# react4.net
KiCad netlist of a schematic drawn in Altium Designer
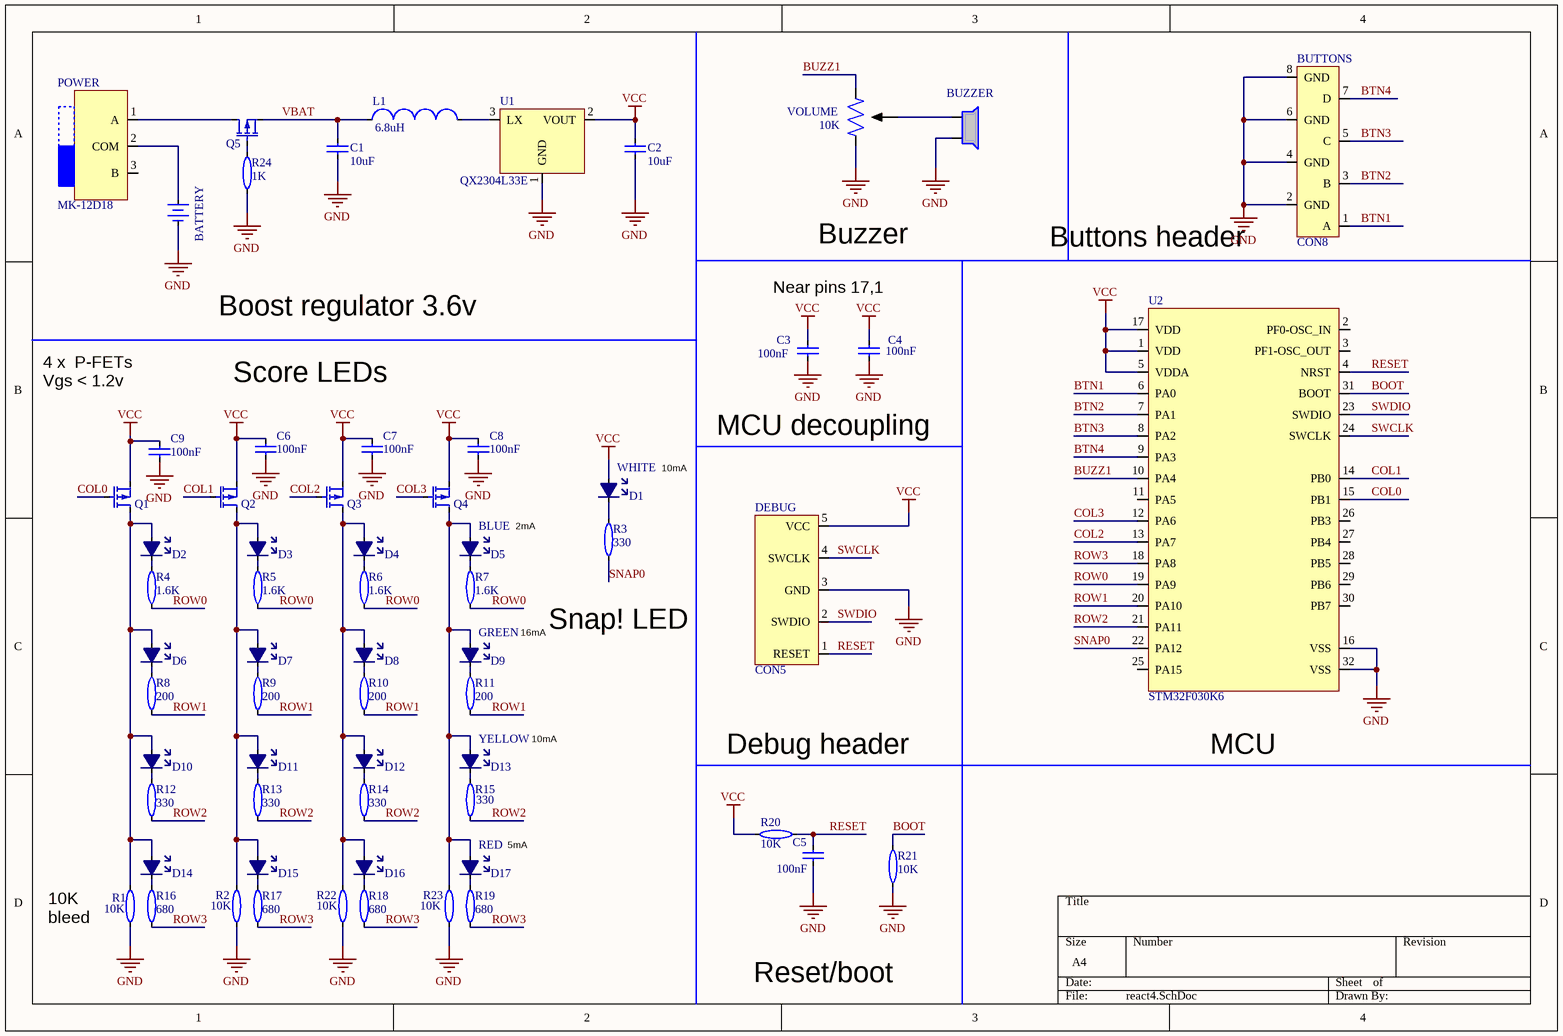
[diagram p0: react4.SchDoc]

(export (version "E")
  (design (tool "Eeschema 10.0.6"))
  (components
    (comp (ref "BATTERY")
      (value "BATTERY")
      (footprint "BATTERY_CONNECTOR")
      (libsource (lib "react4") (part "BATTERY"))
    )
    (comp (ref "BUTTONS")
      (value "CON8")
      (footprint "CON8")
      (description "2 x 4 2.54mm IDC board connector")
      (libsource (lib "react4") (part "CON8"))
    )
    (comp (ref "BUZZER")
      (value "BUZZER")
      (footprint "PIEZO_BUZZER")
      (description "3V 12mm piezo buzzer")
      (libsource (lib "react4") (part "BUZZER"))
    )
    (comp (ref "C1")
      (value "10uF")
      (footprint "CAPC_1206_3216X16L")
      (description "Capacitor")
      (fields (field (name "Comment") "CAPACITOR"))
      (libsource (lib "react4") (part "CAPACITOR"))
    )
    (comp (ref "C2")
      (value "10uF")
      (footprint "CAPC_1206_3216X16L")
      (description "Capacitor")
      (fields (field (name "Comment") "CAPACITOR"))
      (libsource (lib "react4") (part "CAPACITOR"))
    )
    (comp (ref "C3")
      (value "100nF")
      (footprint "CAPC_0603_1608X08L")
      (description "Capacitor")
      (fields (field (name "Comment") "CAPACITOR"))
      (libsource (lib "react4") (part "CAPACITOR"))
    )
    (comp (ref "C4")
      (value "100nF")
      (footprint "CAPC_0603_1608X08L")
      (description "Capacitor")
      (fields (field (name "Comment") "CAPACITOR"))
      (libsource (lib "react4") (part "CAPACITOR"))
    )
    (comp (ref "C5")
      (value "100nF")
      (footprint "CAPC_0603_1608X08L")
      (description "Capacitor")
      (fields (field (name "Comment") "CAPACITOR"))
      (libsource (lib "react4") (part "CAPACITOR"))
    )
    (comp (ref "C6")
      (value "100nF")
      (footprint "CAPC_0603_1608X08L")
      (description "Capacitor")
      (fields (field (name "Comment") "CAPACITOR"))
      (libsource (lib "react4") (part "CAPACITOR"))
    )
    (comp (ref "C7")
      (value "100nF")
      (footprint "CAPC_0603_1608X08L")
      (description "Capacitor")
      (fields (field (name "Comment") "CAPACITOR"))
      (libsource (lib "react4") (part "CAPACITOR"))
    )
    (comp (ref "C8")
      (value "100nF")
      (footprint "CAPC_0603_1608X08L")
      (description "Capacitor")
      (fields (field (name "Comment") "CAPACITOR"))
      (libsource (lib "react4") (part "CAPACITOR"))
    )
    (comp (ref "C9")
      (value "100nF")
      (footprint "CAPC_0603_1608X08L")
      (description "Capacitor")
      (fields (field (name "Comment") "CAPACITOR"))
      (libsource (lib "react4") (part "CAPACITOR"))
    )
    (comp (ref "D1")
      (value "WHITE")
      (footprint "LED WHITE")
      (description "5mm through hole LED")
      (libsource (lib "react4") (part "LED"))
    )
    (comp (ref "D2")
      (value "BLUE")
      (footprint "LED BLUE")
      (description "5mm through hole LED")
      (libsource (lib "react4") (part "LED"))
    )
    (comp (ref "D3")
      (value "BLUE")
      (footprint "LED BLUE")
      (description "5mm through hole LED")
      (libsource (lib "react4") (part "LED"))
    )
    (comp (ref "D4")
      (value "BLUE")
      (footprint "LED BLUE")
      (description "5mm through hole LED")
      (libsource (lib "react4") (part "LED"))
    )
    (comp (ref "D5")
      (value "BLUE")
      (footprint "LED BLUE")
      (description "5mm through hole LED")
      (libsource (lib "react4") (part "LED"))
    )
    (comp (ref "D6")
      (value "GREEN")
      (footprint "LED GREEN")
      (description "5mm through hole LED")
      (libsource (lib "react4") (part "LED"))
    )
    (comp (ref "D7")
      (value "GREEN")
      (footprint "LED GREEN")
      (description "5mm through hole LED")
      (libsource (lib "react4") (part "LED"))
    )
    (comp (ref "D8")
      (value "GREEN")
      (footprint "LED GREEN")
      (description "5mm through hole LED")
      (libsource (lib "react4") (part "LED"))
    )
    (comp (ref "D9")
      (value "GREEN")
      (footprint "LED GREEN")
      (description "5mm through hole LED")
      (libsource (lib "react4") (part "LED"))
    )
    (comp (ref "D10")
      (value "YELLOW")
      (footprint "LED YELLOW")
      (description "5mm through hole LED")
      (libsource (lib "react4") (part "LED"))
    )
    (comp (ref "D11")
      (value "YELLOW")
      (footprint "LED YELLOW")
      (description "5mm through hole LED")
      (libsource (lib "react4") (part "LED"))
    )
    (comp (ref "D12")
      (value "YELLOW")
      (footprint "LED YELLOW")
      (description "5mm through hole LED")
      (libsource (lib "react4") (part "LED"))
    )
    (comp (ref "D13")
      (value "YELLOW")
      (footprint "LED YELLOW")
      (description "5mm through hole LED")
      (libsource (lib "react4") (part "LED"))
    )
    (comp (ref "D14")
      (value "RED")
      (footprint "LED RED")
      (description "5mm through hole LED")
      (libsource (lib "react4") (part "LED"))
    )
    (comp (ref "D15")
      (value "RED")
      (footprint "LED RED")
      (description "5mm through hole LED")
      (libsource (lib "react4") (part "LED"))
    )
    (comp (ref "D16")
      (value "RED")
      (footprint "LED RED")
      (description "5mm through hole LED")
      (libsource (lib "react4") (part "LED"))
    )
    (comp (ref "D17")
      (value "RED")
      (footprint "LED RED")
      (description "5mm through hole LED")
      (libsource (lib "react4") (part "LED"))
    )
    (comp (ref "DEBUG") (value "CON5") (footprint "CON5") (libsource (lib "react4") (part "CON5")))
    (comp (ref "L1")
      (value "6.8uH")
      (footprint "Chip2PinSM127P600-8N")
      (description "200mA 1206 SMD Inductor")
      (fields (field (name "Comment") "INDUCTOR"))
      (libsource (lib "react4") (part "INDUCTOR"))
    )
    (comp (ref "POWER")
      (value "MK-12D18")
      (footprint "MK-12D18")
      (description "DIP,9.1x3.5x3.5mm Toggle Switch")
      (libsource (lib "react4") (part "SPDT SWITCH"))
    )
    (comp (ref "Q1")
      (value "NX2301P")
      (footprint "SOT95P237X110-3L")
      (description "P-MOSFET -20V -2A 400mW NX2301P or equivalent")
      (libsource (lib "react4") (part "MOSFET-P"))
    )
    (comp (ref "Q2")
      (value "NX2301P")
      (footprint "SOT95P237X110-3L")
      (description "P-MOSFET -20V -2A 400mW NX2301P or equivalent")
      (libsource (lib "react4") (part "MOSFET-P"))
    )
    (comp (ref "Q3")
      (value "NX2301P")
      (footprint "SOT95P237X110-3L")
      (description "P-MOSFET -20V -2A 400mW NX2301P or equivalent")
      (libsource (lib "react4") (part "MOSFET-P"))
    )
    (comp (ref "Q4")
      (value "NX2301P")
      (footprint "SOT95P237X110-3L")
      (description "P-MOSFET -20V -2A 400mW NX2301P or equivalent")
      (libsource (lib "react4") (part "MOSFET-P"))
    )
    (comp (ref "Q5")
      (value "NX2301P")
      (footprint "SOT95P237X110-3L")
      (description "P-MOSFET -20V -2A 400mW NX2301P or equivalent")
      (libsource (lib "react4") (part "MOSFET-P"))
    )
    (comp (ref "R1")
      (value "10K")
      (footprint "RESC_0603_1608X08L")
      (description "125mW 0603 SMD resistor")
      (fields (field (name "Comment") "RESISTOR"))
      (libsource (lib "react4") (part "RESISTOR"))
    )
    (comp (ref "R2")
      (value "10K")
      (footprint "RESC_0603_1608X08L")
      (description "125mW 0603 SMD resistor")
      (fields (field (name "Comment") "RESISTOR"))
      (libsource (lib "react4") (part "RESISTOR"))
    )
    (comp (ref "R3")
      (value "330")
      (footprint "RESC_0603_1608X08L")
      (description "125mW 0603 SMD resistor")
      (fields (field (name "Comment") "RESISTOR"))
      (libsource (lib "react4") (part "RESISTOR"))
    )
    (comp (ref "R4")
      (value "1.6K")
      (footprint "RESC_0603_1608X08L")
      (description "125mW 0603 SMD resistor")
      (fields (field (name "Comment") "RESISTOR"))
      (libsource (lib "react4") (part "RESISTOR"))
    )
    (comp (ref "R5")
      (value "1.6K")
      (footprint "RESC_0603_1608X08L")
      (description "125mW 0603 SMD resistor")
      (fields (field (name "Comment") "RESISTOR"))
      (libsource (lib "react4") (part "RESISTOR"))
    )
    (comp (ref "R6")
      (value "1.6K")
      (footprint "RESC_0603_1608X08L")
      (description "125mW 0603 SMD resistor")
      (fields (field (name "Comment") "RESISTOR"))
      (libsource (lib "react4") (part "RESISTOR"))
    )
    (comp (ref "R7")
      (value "1.6K")
      (footprint "RESC_0603_1608X08L")
      (description "125mW 0603 SMD resistor")
      (fields (field (name "Comment") "RESISTOR"))
      (libsource (lib "react4") (part "RESISTOR"))
    )
    (comp (ref "R8")
      (value "200")
      (footprint "RESC_0603_1608X08L")
      (description "125mW 0603 SMD resistor")
      (fields (field (name "Comment") "RESISTOR"))
      (libsource (lib "react4") (part "RESISTOR"))
    )
    (comp (ref "R9")
      (value "200")
      (footprint "RESC_0603_1608X08L")
      (description "125mW 0603 SMD resistor")
      (fields (field (name "Comment") "RESISTOR"))
      (libsource (lib "react4") (part "RESISTOR"))
    )
    (comp (ref "R10")
      (value "200")
      (footprint "RESC_0603_1608X08L")
      (description "125mW 0603 SMD resistor")
      (fields (field (name "Comment") "RESISTOR"))
      (libsource (lib "react4") (part "RESISTOR"))
    )
    (comp (ref "R11")
      (value "200")
      (footprint "RESC_0603_1608X08L")
      (description "125mW 0603 SMD resistor")
      (fields (field (name "Comment") "RESISTOR"))
      (libsource (lib "react4") (part "RESISTOR"))
    )
    (comp (ref "R12")
      (value "330")
      (footprint "RESC_0603_1608X08L")
      (description "125mW 0603 SMD resistor")
      (fields (field (name "Comment") "RESISTOR"))
      (libsource (lib "react4") (part "RESISTOR"))
    )
    (comp (ref "R13")
      (value "330")
      (footprint "RESC_0603_1608X08L")
      (description "125mW 0603 SMD resistor")
      (fields (field (name "Comment") "RESISTOR"))
      (libsource (lib "react4") (part "RESISTOR"))
    )
    (comp (ref "R14")
      (value "330")
      (footprint "RESC_0603_1608X08L")
      (description "125mW 0603 SMD resistor")
      (fields (field (name "Comment") "RESISTOR"))
      (libsource (lib "react4") (part "RESISTOR"))
    )
    (comp (ref "R15")
      (value "330")
      (footprint "RESC_0603_1608X08L")
      (description "125mW 0603 SMD resistor")
      (fields (field (name "Comment") "RESISTOR"))
      (libsource (lib "react4") (part "RESISTOR"))
    )
    (comp (ref "R16")
      (value "680")
      (footprint "RESC_0603_1608X08L")
      (description "125mW 0603 SMD resistor")
      (fields (field (name "Comment") "RESISTOR"))
      (libsource (lib "react4") (part "RESISTOR"))
    )
    (comp (ref "R17")
      (value "680")
      (footprint "RESC_0603_1608X08L")
      (description "125mW 0603 SMD resistor")
      (fields (field (name "Comment") "RESISTOR"))
      (libsource (lib "react4") (part "RESISTOR"))
    )
    (comp (ref "R18")
      (value "680")
      (footprint "RESC_0603_1608X08L")
      (description "125mW 0603 SMD resistor")
      (fields (field (name "Comment") "RESISTOR"))
      (libsource (lib "react4") (part "RESISTOR"))
    )
    (comp (ref "R19")
      (value "680")
      (footprint "RESC_0603_1608X08L")
      (description "125mW 0603 SMD resistor")
      (fields (field (name "Comment") "RESISTOR"))
      (libsource (lib "react4") (part "RESISTOR"))
    )
    (comp (ref "R20")
      (value "10K")
      (footprint "RESC_0603_1608X08L")
      (description "125mW 0603 SMD resistor")
      (fields (field (name "Comment") "RESISTOR"))
      (libsource (lib "react4") (part "RESISTOR"))
    )
    (comp (ref "R21")
      (value "10K")
      (footprint "RESC_0603_1608X08L")
      (description "125mW 0603 SMD resistor")
      (fields (field (name "Comment") "RESISTOR"))
      (libsource (lib "react4") (part "RESISTOR"))
    )
    (comp (ref "R22")
      (value "10K")
      (footprint "RESC_0603_1608X08L")
      (description "125mW 0603 SMD resistor")
      (fields (field (name "Comment") "RESISTOR"))
      (libsource (lib "react4") (part "RESISTOR"))
    )
    (comp (ref "R23")
      (value "10K")
      (footprint "RESC_0603_1608X08L")
      (description "125mW 0603 SMD resistor")
      (fields (field (name "Comment") "RESISTOR"))
      (libsource (lib "react4") (part "RESISTOR"))
    )
    (comp (ref "R24")
      (value "1K")
      (footprint "RESC_0603_1608X08L")
      (description "125mW 0603 SMD resistor")
      (fields (field (name "Comment") "RESISTOR"))
      (libsource (lib "react4") (part "RESISTOR"))
    )
    (comp (ref "U1")
      (value "QX2304L33E")
      (footprint "SOT89-150P350X160-3L")
      (description "3.3v boost regulator 1A 0.5W")
      (libsource (lib "react4") (part "QX2304L33E"))
    )
    (comp (ref "U2")
      (value "STM32F030K6")
      (footprint "TQFP80P900X900X160-32L")
      (description "STM32F030K6 QFP32 48MHz")
      (libsource (lib "react4") (part "STM32F030K6"))
    )
    (comp (ref "VOLUME")
      (value "10K")
      (footprint "POTENTIOMETER")
      (description "10K audio pot 16x2mm thumbwheel")
      (fields (field (name "Comment") "POTENTIOMETER"))
      (libsource (lib "react4") (part "POTENTIOMETER"))
    )
  )
  (nets
    (net (code "1") (name "/BOOT") (class "Default")
      (node (ref "R21") (pin "1") (pinfunction "1_1") (pintype "passive"))
      (node (ref "U2") (pin "31") (pinfunction "BOOT_31") (pintype "power_in"))
    )
    (net (code "2") (name "/BTN1") (class "Default")
      (node (ref "BUTTONS") (pin "1") (pinfunction "A_1") (pintype "power_in"))
      (node (ref "U2") (pin "6") (pinfunction "PA0_6") (pintype "power_in"))
    )
    (net (code "3") (name "/BTN2") (class "Default")
      (node (ref "BUTTONS") (pin "3") (pinfunction "B_3") (pintype "power_in"))
      (node (ref "U2") (pin "7") (pinfunction "PA1_7") (pintype "power_in"))
    )
    (net (code "4") (name "/BTN3") (class "Default")
      (node (ref "BUTTONS") (pin "5") (pinfunction "C_5") (pintype "power_in"))
      (node (ref "U2") (pin "8") (pinfunction "PA2_8") (pintype "power_in"))
    )
    (net (code "5") (name "/BTN4") (class "Default")
      (node (ref "BUTTONS") (pin "7") (pinfunction "D_7") (pintype "power_in"))
      (node (ref "U2") (pin "9") (pinfunction "PA3_9") (pintype "power_in"))
    )
    (net (code "6") (name "/BUZZ1") (class "Default")
      (node (ref "U2") (pin "10") (pinfunction "PA4_10") (pintype "power_in"))
      (node (ref "VOLUME") (pin "1") (pinfunction "1_1") (pintype "power_in"))
    )
    (net (code "7") (name "/COL0") (class "Default")
      (node (ref "Q1") (pin "1") (pinfunction "G_1") (pintype "passive"))
      (node (ref "U2") (pin "15") (pinfunction "PB1_15") (pintype "power_in"))
    )
    (net (code "8") (name "/COL1") (class "Default")
      (node (ref "Q2") (pin "1") (pinfunction "G_1") (pintype "passive"))
      (node (ref "U2") (pin "14") (pinfunction "PB0_14") (pintype "power_in"))
    )
    (net (code "9") (name "/COL2") (class "Default")
      (node (ref "Q3") (pin "1") (pinfunction "G_1") (pintype "passive"))
      (node (ref "U2") (pin "13") (pinfunction "PA7_13") (pintype "power_in"))
    )
    (net (code "10") (name "/COL3") (class "Default")
      (node (ref "Q4") (pin "1") (pinfunction "G_1") (pintype "passive"))
      (node (ref "U2") (pin "12") (pinfunction "PA6_12") (pintype "power_in"))
    )
    (net (code "11") (name "/RESET") (class "Default")
      (node (ref "C5") (pin "2") (pinfunction "2_2") (pintype "passive"))
      (node (ref "DEBUG") (pin "1") (pinfunction "RESET_1") (pintype "power_in"))
      (node (ref "R20") (pin "1") (pinfunction "1_1") (pintype "passive"))
      (node (ref "U2") (pin "4") (pinfunction "NRST_4") (pintype "power_in"))
    )
    (net (code "12") (name "/ROW0") (class "Default")
      (node (ref "R4") (pin "1") (pinfunction "1_1") (pintype "passive"))
      (node (ref "R5") (pin "1") (pinfunction "1_1") (pintype "passive"))
      (node (ref "R6") (pin "1") (pinfunction "1_1") (pintype "passive"))
      (node (ref "R7") (pin "1") (pinfunction "1_1") (pintype "passive"))
      (node (ref "U2") (pin "19") (pinfunction "PA9_19") (pintype "power_in"))
    )
    (net (code "13") (name "/ROW1") (class "Default")
      (node (ref "R10") (pin "1") (pinfunction "1_1") (pintype "passive"))
      (node (ref "R11") (pin "1") (pinfunction "1_1") (pintype "passive"))
      (node (ref "R8") (pin "1") (pinfunction "1_1") (pintype "passive"))
      (node (ref "R9") (pin "1") (pinfunction "1_1") (pintype "passive"))
      (node (ref "U2") (pin "20") (pinfunction "PA10_20") (pintype "power_in"))
    )
    (net (code "14") (name "/ROW2") (class "Default")
      (node (ref "R12") (pin "1") (pinfunction "1_1") (pintype "passive"))
      (node (ref "R13") (pin "1") (pinfunction "1_1") (pintype "passive"))
      (node (ref "R14") (pin "1") (pinfunction "1_1") (pintype "passive"))
      (node (ref "R15") (pin "1") (pinfunction "1_1") (pintype "passive"))
      (node (ref "U2") (pin "21") (pinfunction "PA11_21") (pintype "power_in"))
    )
    (net (code "15") (name "/ROW3") (class "Default")
      (node (ref "R16") (pin "1") (pinfunction "1_1") (pintype "passive"))
      (node (ref "R17") (pin "1") (pinfunction "1_1") (pintype "passive"))
      (node (ref "R18") (pin "1") (pinfunction "1_1") (pintype "passive"))
      (node (ref "R19") (pin "1") (pinfunction "1_1") (pintype "passive"))
      (node (ref "U2") (pin "18") (pinfunction "PA8_18") (pintype "power_in"))
    )
    (net (code "16") (name "/SNAP0") (class "Default")
      (node (ref "R3") (pin "1") (pinfunction "1_1") (pintype "passive"))
      (node (ref "U2") (pin "22") (pinfunction "PA12_22") (pintype "power_in"))
    )
    (net (code "17") (name "/SWCLK") (class "Default")
      (node (ref "DEBUG") (pin "4") (pinfunction "SWCLK_4") (pintype "power_in"))
      (node (ref "U2") (pin "24") (pinfunction "SWCLK_24") (pintype "power_in"))
    )
    (net (code "18") (name "/SWDIO") (class "Default")
      (node (ref "DEBUG") (pin "2") (pinfunction "SWDIO_2") (pintype "power_in"))
      (node (ref "U2") (pin "23") (pinfunction "SWDIO_23") (pintype "power_in"))
    )
    (net (code "19") (name "/VBAT") (class "Default")
      (node (ref "C1") (pin "2") (pinfunction "2_2") (pintype "passive"))
      (node (ref "L1") (pin "1") (pinfunction "1_1") (pintype "passive"))
      (node (ref "Q5") (pin "2") (pinfunction "S_2") (pintype "passive"))
    )
    (net (code "20") (name "GND") (class "Default")
      (node (ref "BATTERY") (pin "1") (pinfunction "NEGATIVE_1") (pintype "power_in"))
      (node (ref "BUTTONS") (pin "2") (pinfunction "GND_2") (pintype "power_in"))
      (node (ref "BUTTONS") (pin "4") (pinfunction "GND_4") (pintype "power_in"))
      (node (ref "BUTTONS") (pin "6") (pinfunction "GND_6") (pintype "power_in"))
      (node (ref "BUTTONS") (pin "8") (pinfunction "GND_8") (pintype "power_in"))
      (node (ref "BUZZER") (pin "2") (pinfunction "2_2") (pintype "passive"))
      (node (ref "C1") (pin "1") (pinfunction "1_1") (pintype "passive"))
      (node (ref "C2") (pin "1") (pinfunction "1_1") (pintype "passive"))
      (node (ref "C3") (pin "1") (pinfunction "1_1") (pintype "passive"))
      (node (ref "C4") (pin "1") (pinfunction "1_1") (pintype "passive"))
      (node (ref "C5") (pin "1") (pinfunction "1_1") (pintype "passive"))
      (node (ref "C6") (pin "1") (pinfunction "1_1") (pintype "passive"))
      (node (ref "C7") (pin "1") (pinfunction "1_1") (pintype "passive"))
      (node (ref "C8") (pin "1") (pinfunction "1_1") (pintype "passive"))
      (node (ref "C9") (pin "1") (pinfunction "1_1") (pintype "passive"))
      (node (ref "DEBUG") (pin "3") (pinfunction "GND_3") (pintype "power_in"))
      (node (ref "R1") (pin "2") (pinfunction "2_2") (pintype "passive"))
      (node (ref "R2") (pin "2") (pinfunction "2_2") (pintype "passive"))
      (node (ref "R21") (pin "2") (pinfunction "2_2") (pintype "passive"))
      (node (ref "R22") (pin "2") (pinfunction "2_2") (pintype "passive"))
      (node (ref "R23") (pin "2") (pinfunction "2_2") (pintype "passive"))
      (node (ref "R24") (pin "1") (pinfunction "1_1") (pintype "passive"))
      (node (ref "U1") (pin "1") (pinfunction "GND_1") (pintype "power_in"))
      (node (ref "U2") (pin "16") (pinfunction "VSS_16") (pintype "power_in"))
      (node (ref "U2") (pin "32") (pinfunction "VSS_32") (pintype "power_in"))
      (node (ref "VOLUME") (pin "3") (pinfunction "3_3") (pintype "power_in"))
    )
    (net (code "21") (name "Net-(BATTERY-POSITIVE)") (class "Default")
      (node (ref "BATTERY") (pin "2") (pinfunction "POSITIVE_2") (pintype "power_in"))
      (node (ref "POWER") (pin "2") (pinfunction "COM_2") (pintype "power_in"))
    )
    (net (code "22") (name "Net-(BUZZER-Pad1)") (class "Default")
      (node (ref "BUZZER") (pin "1") (pinfunction "1_1") (pintype "passive"))
      (node (ref "VOLUME") (pin "2") (pinfunction "2_2") (pintype "power_in"))
    )
    (net (code "23") (name "Net-(D1-C)") (class "Default")
      (node (ref "D1") (pin "1") (pinfunction "C_1") (pintype "passive"))
      (node (ref "R3") (pin "2") (pinfunction "2_2") (pintype "passive"))
    )
    (net (code "24") (name "Net-(D2-C)") (class "Default")
      (node (ref "D2") (pin "1") (pinfunction "C_1") (pintype "passive"))
      (node (ref "R4") (pin "2") (pinfunction "2_2") (pintype "passive"))
    )
    (net (code "25") (name "Net-(D3-C)") (class "Default")
      (node (ref "D3") (pin "1") (pinfunction "C_1") (pintype "passive"))
      (node (ref "R5") (pin "2") (pinfunction "2_2") (pintype "passive"))
    )
    (net (code "26") (name "Net-(D4-C)") (class "Default")
      (node (ref "D4") (pin "1") (pinfunction "C_1") (pintype "passive"))
      (node (ref "R6") (pin "2") (pinfunction "2_2") (pintype "passive"))
    )
    (net (code "27") (name "Net-(D5-C)") (class "Default")
      (node (ref "D5") (pin "1") (pinfunction "C_1") (pintype "passive"))
      (node (ref "R7") (pin "2") (pinfunction "2_2") (pintype "passive"))
    )
    (net (code "28") (name "Net-(D6-C)") (class "Default")
      (node (ref "D6") (pin "1") (pinfunction "C_1") (pintype "passive"))
      (node (ref "R8") (pin "2") (pinfunction "2_2") (pintype "passive"))
    )
    (net (code "29") (name "Net-(D7-C)") (class "Default")
      (node (ref "D7") (pin "1") (pinfunction "C_1") (pintype "passive"))
      (node (ref "R9") (pin "2") (pinfunction "2_2") (pintype "passive"))
    )
    (net (code "30") (name "Net-(D8-C)") (class "Default")
      (node (ref "D8") (pin "1") (pinfunction "C_1") (pintype "passive"))
      (node (ref "R10") (pin "2") (pinfunction "2_2") (pintype "passive"))
    )
    (net (code "31") (name "Net-(D9-C)") (class "Default")
      (node (ref "D9") (pin "1") (pinfunction "C_1") (pintype "passive"))
      (node (ref "R11") (pin "2") (pinfunction "2_2") (pintype "passive"))
    )
    (net (code "32") (name "Net-(D10-A)") (class "Default")
      (node (ref "D10") (pin "2") (pinfunction "A_2") (pintype "passive"))
      (node (ref "D14") (pin "2") (pinfunction "A_2") (pintype "passive"))
      (node (ref "D2") (pin "2") (pinfunction "A_2") (pintype "passive"))
      (node (ref "D6") (pin "2") (pinfunction "A_2") (pintype "passive"))
      (node (ref "Q1") (pin "3") (pinfunction "D_3") (pintype "passive"))
      (node (ref "R1") (pin "1") (pinfunction "1_1") (pintype "passive"))
    )
    (net (code "33") (name "Net-(D10-C)") (class "Default")
      (node (ref "D10") (pin "1") (pinfunction "C_1") (pintype "passive"))
      (node (ref "R12") (pin "2") (pinfunction "2_2") (pintype "passive"))
    )
    (net (code "34") (name "Net-(D11-A)") (class "Default")
      (node (ref "D11") (pin "2") (pinfunction "A_2") (pintype "passive"))
      (node (ref "D15") (pin "2") (pinfunction "A_2") (pintype "passive"))
      (node (ref "D3") (pin "2") (pinfunction "A_2") (pintype "passive"))
      (node (ref "D7") (pin "2") (pinfunction "A_2") (pintype "passive"))
      (node (ref "Q2") (pin "3") (pinfunction "D_3") (pintype "passive"))
      (node (ref "R2") (pin "1") (pinfunction "1_1") (pintype "passive"))
    )
    (net (code "35") (name "Net-(D11-C)") (class "Default")
      (node (ref "D11") (pin "1") (pinfunction "C_1") (pintype "passive"))
      (node (ref "R13") (pin "2") (pinfunction "2_2") (pintype "passive"))
    )
    (net (code "36") (name "Net-(D12-A)") (class "Default")
      (node (ref "D12") (pin "2") (pinfunction "A_2") (pintype "passive"))
      (node (ref "D16") (pin "2") (pinfunction "A_2") (pintype "passive"))
      (node (ref "D4") (pin "2") (pinfunction "A_2") (pintype "passive"))
      (node (ref "D8") (pin "2") (pinfunction "A_2") (pintype "passive"))
      (node (ref "Q3") (pin "3") (pinfunction "D_3") (pintype "passive"))
      (node (ref "R22") (pin "1") (pinfunction "1_1") (pintype "passive"))
    )
    (net (code "37") (name "Net-(D12-C)") (class "Default")
      (node (ref "D12") (pin "1") (pinfunction "C_1") (pintype "passive"))
      (node (ref "R14") (pin "2") (pinfunction "2_2") (pintype "passive"))
    )
    (net (code "38") (name "Net-(D13-A)") (class "Default")
      (node (ref "D13") (pin "2") (pinfunction "A_2") (pintype "passive"))
      (node (ref "D17") (pin "2") (pinfunction "A_2") (pintype "passive"))
      (node (ref "D5") (pin "2") (pinfunction "A_2") (pintype "passive"))
      (node (ref "D9") (pin "2") (pinfunction "A_2") (pintype "passive"))
      (node (ref "Q4") (pin "3") (pinfunction "D_3") (pintype "passive"))
      (node (ref "R23") (pin "1") (pinfunction "1_1") (pintype "passive"))
    )
    (net (code "39") (name "Net-(D13-C)") (class "Default")
      (node (ref "D13") (pin "1") (pinfunction "C_1") (pintype "passive"))
      (node (ref "R15") (pin "2") (pinfunction "2_2") (pintype "passive"))
    )
    (net (code "40") (name "Net-(D14-C)") (class "Default")
      (node (ref "D14") (pin "1") (pinfunction "C_1") (pintype "passive"))
      (node (ref "R16") (pin "2") (pinfunction "2_2") (pintype "passive"))
    )
    (net (code "41") (name "Net-(D15-C)") (class "Default")
      (node (ref "D15") (pin "1") (pinfunction "C_1") (pintype "passive"))
      (node (ref "R17") (pin "2") (pinfunction "2_2") (pintype "passive"))
    )
    (net (code "42") (name "Net-(D16-C)") (class "Default")
      (node (ref "D16") (pin "1") (pinfunction "C_1") (pintype "passive"))
      (node (ref "R18") (pin "2") (pinfunction "2_2") (pintype "passive"))
    )
    (net (code "43") (name "Net-(D17-C)") (class "Default")
      (node (ref "D17") (pin "1") (pinfunction "C_1") (pintype "passive"))
      (node (ref "R19") (pin "2") (pinfunction "2_2") (pintype "passive"))
    )
    (net (code "44") (name "Net-(POWER-A)") (class "Default")
      (node (ref "POWER") (pin "1") (pinfunction "A_1") (pintype "power_in"))
      (node (ref "Q5") (pin "3") (pinfunction "D_3") (pintype "passive"))
    )
    (net (code "45") (name "Net-(Q5-G)") (class "Default")
      (node (ref "Q5") (pin "1") (pinfunction "G_1") (pintype "passive"))
      (node (ref "R24") (pin "2") (pinfunction "2_2") (pintype "passive"))
    )
    (net (code "46") (name "Net-(U1-LX)") (class "Default")
      (node (ref "L1") (pin "2") (pinfunction "2_2") (pintype "passive"))
      (node (ref "U1") (pin "3") (pinfunction "LX_3") (pintype "power_in"))
    )
    (net (code "47") (name "VCC") (class "Default")
      (node (ref "C2") (pin "2") (pinfunction "2_2") (pintype "passive"))
      (node (ref "C3") (pin "2") (pinfunction "2_2") (pintype "passive"))
      (node (ref "C4") (pin "2") (pinfunction "2_2") (pintype "passive"))
      (node (ref "C6") (pin "2") (pinfunction "2_2") (pintype "passive"))
      (node (ref "C7") (pin "2") (pinfunction "2_2") (pintype "passive"))
      (node (ref "C8") (pin "2") (pinfunction "2_2") (pintype "passive"))
      (node (ref "C9") (pin "2") (pinfunction "2_2") (pintype "passive"))
      (node (ref "D1") (pin "2") (pinfunction "A_2") (pintype "passive"))
      (node (ref "DEBUG") (pin "5") (pinfunction "VCC_5") (pintype "power_in"))
      (node (ref "Q1") (pin "2") (pinfunction "S_2") (pintype "passive"))
      (node (ref "Q2") (pin "2") (pinfunction "S_2") (pintype "passive"))
      (node (ref "Q3") (pin "2") (pinfunction "S_2") (pintype "passive"))
      (node (ref "Q4") (pin "2") (pinfunction "S_2") (pintype "passive"))
      (node (ref "R20") (pin "2") (pinfunction "2_2") (pintype "passive"))
      (node (ref "U1") (pin "2") (pinfunction "VOUT_2") (pintype "power_in"))
      (node (ref "U2") (pin "1") (pinfunction "VDD_1") (pintype "power_in"))
      (node (ref "U2") (pin "17") (pinfunction "VDD_17") (pintype "power_in"))
      (node (ref "U2") (pin "5") (pinfunction "VDDA_5") (pintype "power_in"))
    )
    (net (code "48") (name "unconnected-(POWER-B-Pad3)") (class "Default")
      (node (ref "POWER") (pin "3") (pinfunction "B_3") (pintype "power_in"))
    )
    (net (code "49") (name "unconnected-(U2-PA5-Pad11)") (class "Default")
      (node (ref "U2") (pin "11") (pinfunction "PA5_11") (pintype "power_in"))
    )
    (net (code "50") (name "unconnected-(U2-PA15-Pad25)") (class "Default")
      (node (ref "U2") (pin "25") (pinfunction "PA15_25") (pintype "power_in"))
    )
    (net (code "51") (name "unconnected-(U2-PB3-Pad26)") (class "Default")
      (node (ref "U2") (pin "26") (pinfunction "PB3_26") (pintype "power_in"))
    )
    (net (code "52") (name "unconnected-(U2-PB4-Pad27)") (class "Default")
      (node (ref "U2") (pin "27") (pinfunction "PB4_27") (pintype "power_in"))
    )
    (net (code "53") (name "unconnected-(U2-PB5-Pad28)") (class "Default")
      (node (ref "U2") (pin "28") (pinfunction "PB5_28") (pintype "power_in"))
    )
    (net (code "54") (name "unconnected-(U2-PB6-Pad29)") (class "Default")
      (node (ref "U2") (pin "29") (pinfunction "PB6_29") (pintype "power_in"))
    )
    (net (code "55") (name "unconnected-(U2-PB7-Pad30)") (class "Default")
      (node (ref "U2") (pin "30") (pinfunction "PB7_30") (pintype "power_in"))
    )
    (net (code "56") (name "unconnected-(U2-PF0-OSC_IN-Pad2)") (class "Default")
      (node (ref "U2") (pin "2") (pinfunction "PF0-OSC_IN_2") (pintype "power_in"))
    )
    (net (code "57") (name "unconnected-(U2-PF1-OSC_OUT-Pad3)") (class "Default")
      (node (ref "U2") (pin "3") (pinfunction "PF1-OSC_OUT_3") (pintype "power_in"))
    )
  )
)
